# External_Temp_Sensor.net
KiCad netlist of a schematic drawn in Altium Designer
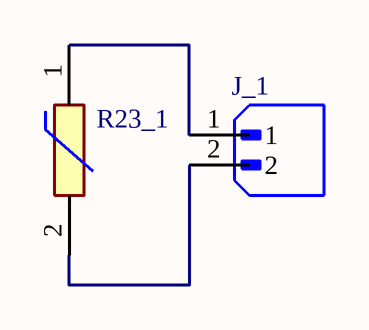
[diagram p0: External Temp Sensor.SchDoc]

(export (version "E")
  (design (tool "Eeschema 10.0.6"))
  (components
    (comp (ref "J_1")
      (value "B2B-XH-A(LF)(SN)")
      (footprint "JST_B2B-XH-A(LF)(SN)")
      (description "Connector Header Through Hole 2 position 0.098 (2.50mm)")
      (fields (field (name "MF") "JST Sales America Inc."))
      (libsource (lib "B2B-XH-A_LF__SN_") (part "B2B-XH-A(LF)(SN)"))
    )
    (comp (ref "R23_1")
      (value "NTCS0805E3104GMT")
      (footprint "SamacSys:THRMC2012X95N")
      (description "Thermistor")
      (fields (field (name "MOUSER PART NUMBER") "594-NTCS0805E3104GMT"))
      (libsource (lib "*") (part "NTCS0805E3104GMT"))
    )
  )
  (nets
    (net (code "1") (name "Net-(J_1-Pad1)") (class "Default")
      (node (ref "J_1") (pin "1") (pinfunction "1_1") (pintype "passive"))
      (node (ref "R23_1") (pin "1") (pinfunction "1_1") (pintype "passive"))
    )
    (net (code "2") (name "Net-(J_1-Pad2)") (class "Default")
      (node (ref "J_1") (pin "2") (pinfunction "2_2") (pintype "passive"))
      (node (ref "R23_1") (pin "2") (pinfunction "2_2") (pintype "passive"))
    )
  )
)
